# INDICATOR_MEZ.net
KiCad netlist of a schematic drawn in Altium Designer
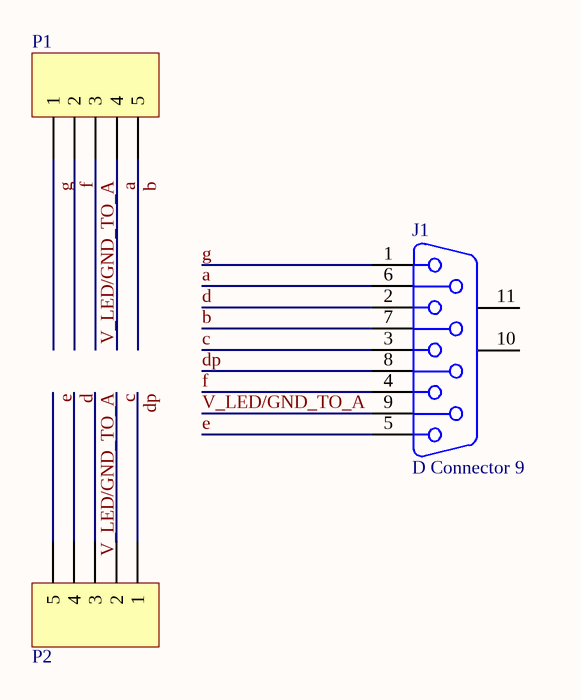
[diagram p0: INDICATOR_MEZ.SchDoc]

(export (version "E")
  (design (tool "Eeschema 10.0.6"))
  (components
    (comp (ref "J1")
      (value "D Connector 9")
      (footprint "DSUB1.385-2H9")
      (description "Receptacle Assembly, 9 Position, Right Angle")
      (fields (field (name "PUBLISHER") "Altium Limited"))
      (libsource (lib "Miscellaneous Connectors") (part "D Connector 9"))
    )
    (comp (ref "P1")
      (value "Header 5")
      (footprint "HDR1X5")
      (description "Header, 5-Pin")
      (fields (field (name "PUBLISHER") "Altium Limited"))
      (libsource (lib "Miscellaneous Connectors") (part "Header 5"))
    )
    (comp (ref "P2")
      (value "Header 5")
      (footprint "HDR1X5")
      (description "Header, 5-Pin")
      (fields (field (name "PUBLISHER") "Altium Limited"))
      (libsource (lib "") (part "Header 5_1"))
    )
  )
  (nets
    (net (code "1") (name "/V_LED{slash}GND_TO_A") (class "Default")
      (node (ref "J1") (pin "9") (pinfunction "9_9") (pintype "passive"))
      (node (ref "P1") (pin "3") (pinfunction "3_3") (pintype "passive"))
      (node (ref "P2") (pin "3") (pinfunction "3_3") (pintype "passive"))
    )
    (net (code "2") (name "/a") (class "Default")
      (node (ref "J1") (pin "6") (pinfunction "6_6") (pintype "passive"))
      (node (ref "P1") (pin "4") (pinfunction "4_4") (pintype "passive"))
    )
    (net (code "3") (name "/b") (class "Default")
      (node (ref "J1") (pin "7") (pinfunction "7_7") (pintype "passive"))
      (node (ref "P1") (pin "5") (pinfunction "5_5") (pintype "passive"))
    )
    (net (code "4") (name "/c") (class "Default")
      (node (ref "J1") (pin "3") (pinfunction "3_3") (pintype "passive"))
      (node (ref "P2") (pin "2") (pinfunction "2_2") (pintype "passive"))
    )
    (net (code "5") (name "/d") (class "Default")
      (node (ref "J1") (pin "2") (pinfunction "2_2") (pintype "passive"))
      (node (ref "P2") (pin "4") (pinfunction "4_4") (pintype "passive"))
    )
    (net (code "6") (name "/dp") (class "Default")
      (node (ref "J1") (pin "8") (pinfunction "8_8") (pintype "passive"))
      (node (ref "P2") (pin "1") (pinfunction "1_1") (pintype "passive"))
    )
    (net (code "7") (name "/e") (class "Default")
      (node (ref "J1") (pin "5") (pinfunction "5_5") (pintype "passive"))
      (node (ref "P2") (pin "5") (pinfunction "5_5") (pintype "passive"))
    )
    (net (code "8") (name "/f") (class "Default")
      (node (ref "J1") (pin "4") (pinfunction "4_4") (pintype "passive"))
      (node (ref "P1") (pin "2") (pinfunction "2_2") (pintype "passive"))
    )
    (net (code "9") (name "/g") (class "Default")
      (node (ref "J1") (pin "1") (pinfunction "1_1") (pintype "passive"))
      (node (ref "P1") (pin "1") (pinfunction "1_1") (pintype "passive"))
    )
    (net (code "10") (name "unconnected-(J1-MH1-Pad10)") (class "Default")
      (node (ref "J1") (pin "10") (pinfunction "MH1_10") (pintype "passive"))
    )
    (net (code "11") (name "unconnected-(J1-MH2-Pad11)") (class "Default")
      (node (ref "J1") (pin "11") (pinfunction "MH2_11") (pintype "passive"))
    )
  )
)
